# netnode_v3.net
KiCad netlist of a schematic drawn in EAGLE
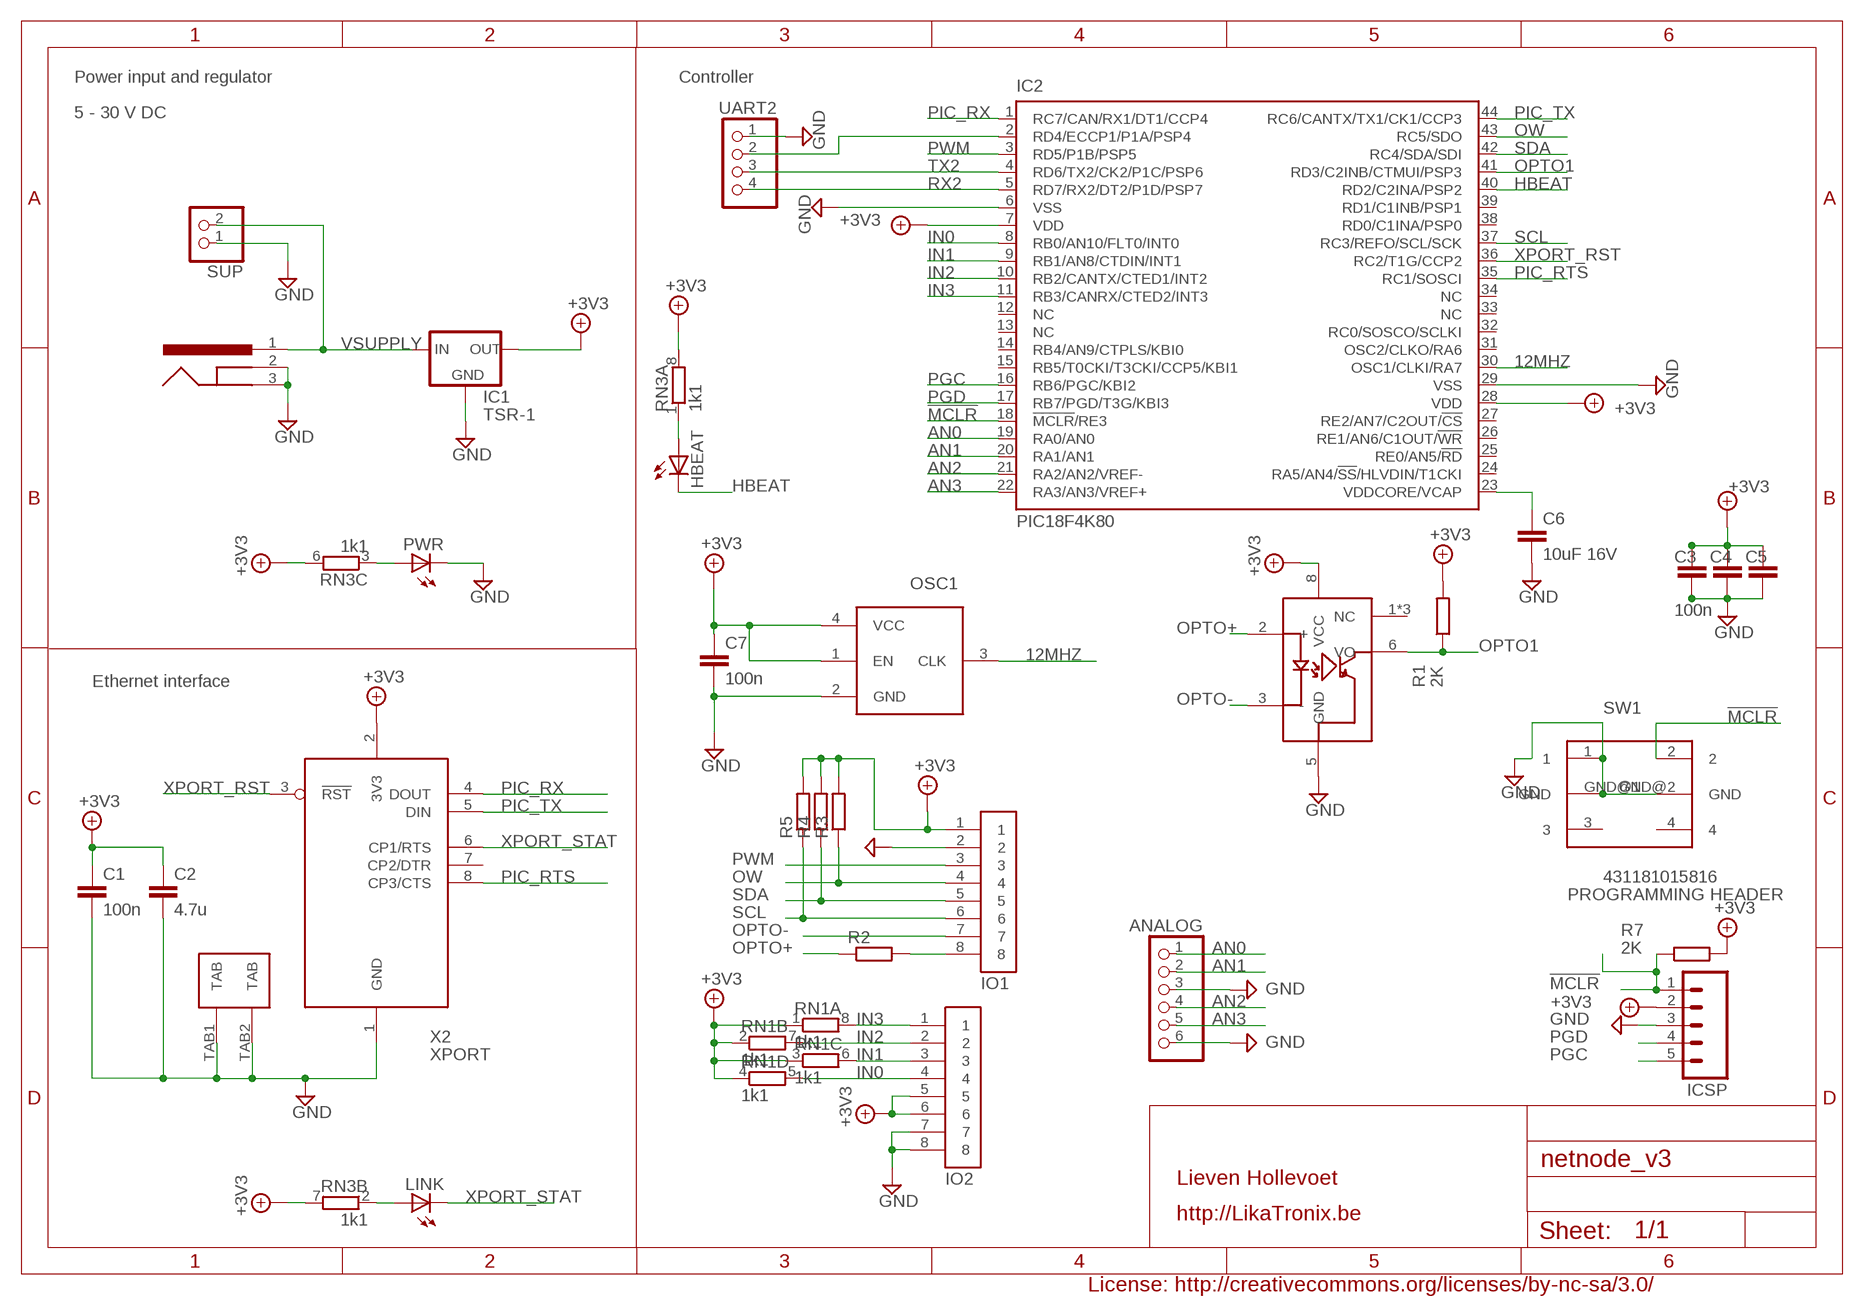
[diagram p0: schematic, sheet 1]

(export (version "E")
  (design (tool "Eeschema 10.0.6"))
  (components
    (comp (ref "ANALOG")
      (value "PINHD-1X6")
      (footprint "eagle-import:1X06")
      (libsource (lib "eagle-import") (part "PINHD-1X6"))
    )
    (comp (ref "C1")
      (value "100n")
      (footprint "eagle-import:C0805")
      (fields (field (name "MF") "AVX") (field (name "MPN") "08055C104JAT2A"))
      (libsource (lib "eagle-import") (part "rcl_C-EUC0805"))
    )
    (comp (ref "C2")
      (value "4.7u")
      (footprint "eagle-import:C0805")
      (fields (field (name "MF") "AVX") (field (name "MPN") "0805YD475KAT2A"))
      (libsource (lib "eagle-import") (part "C-EUC0805"))
    )
    (comp (ref "C3")
      (value "100n")
      (footprint "eagle-import:C0805")
      (fields (field (name "MF") "AVX") (field (name "MPN") "08055C104JAT2A"))
      (libsource (lib "eagle-import") (part "rcl_C-EUC0805"))
    )
    (comp (ref "C4")
      (value "100n")
      (footprint "eagle-import:C0805")
      (fields (field (name "MF") "AVX") (field (name "MPN") "08055C104JAT2A"))
      (libsource (lib "eagle-import") (part "rcl_C-EUC0805"))
    )
    (comp (ref "C5")
      (value "100n")
      (footprint "eagle-import:C0805")
      (fields (field (name "MF") "AVX") (field (name "MPN") "08055C104JAT2A"))
      (libsource (lib "eagle-import") (part "rcl_C-EUC0805"))
    )
    (comp (ref "C6")
      (value "10uF 16V")
      (footprint "eagle-import:C1206")
      (fields (field (name "MF") "KEMET") (field (name "MPN") "C1206C106K4PAC-TU"))
      (libsource (lib "eagle-import") (part "C-EUC1206"))
    )
    (comp (ref "C7")
      (value "100n")
      (footprint "eagle-import:C0805")
      (fields (field (name "MF") "AVX") (field (name "MPN") "08055C104JAT2A"))
      (libsource (lib "eagle-import") (part "rcl_C-EUC0805"))
    )
    (comp (ref "HBEAT")
      (value "LEDCHIPLED_1206")
      (footprint "eagle-import:CHIPLED_1206")
      (fields (field (name "MF") "KINGBRIGHT") (field (name "MPN") "KP-3216EC"))
      (libsource (lib "eagle-import") (part "LEDCHIPLED_1206"))
    )
    (comp (ref "IC1")
      (value "TSR-1")
      (footprint "eagle-import:TSR1-SIPS")
      (fields (field (name "MF") "TRACOPOWER") (field (name "MPN") "TSR 1-2433"))
      (libsource (lib "eagle-import") (part "TSR-1"))
    )
    (comp (ref "IC2")
      (value "PIC18F4K80")
      (footprint "eagle-import:TQFP44")
      (fields (field (name "MF") "MICROCHIP") (field (name "MPN") "PIC18F45K80-I/PT"))
      (libsource (lib "eagle-import") (part "PIC18F4K80"))
    )
    (comp (ref "IC3")
      (value "FOD060L")
      (footprint "eagle-import:SO-08")
      (libsource (lib "eagle-import") (part "FOD060L"))
    )
    (comp (ref "ICSP")
      (value "ICSP")
      (footprint "eagle-import:1X05")
      (libsource (lib "eagle-import") (part "M05"))
    )
    (comp (ref "IO1")
      (value "SCREW_TERMINAL")
      (footprint "eagle-import:SCREW_TERMINAL_8PINS")
      (fields (field (name "MF") "PHOENIX CONTACT") (field (name "MPN") "1725711"))
      (libsource (lib "eagle-import") (part "SCREW_TERMINAL"))
    )
    (comp (ref "IO2")
      (value "SCREW_TERMINAL")
      (footprint "eagle-import:SCREW_TERMINAL_8PINS")
      (fields (field (name "MF") "PHOENIX CONTACT") (field (name "MPN") "1725711"))
      (libsource (lib "eagle-import") (part "SCREW_TERMINAL"))
    )
    (comp (ref "LINK")
      (value "LEDCHIPLED_1206")
      (footprint "eagle-import:CHIPLED_1206")
      (fields (field (name "MF") "KINGBRIGHT") (field (name "MPN") "KP-3216EC"))
      (libsource (lib "eagle-import") (part "LEDCHIPLED_1206"))
    )
    (comp (ref "OSC1")
      (value "TXC - 7X-12.000MBB-T")
      (footprint "eagle-import:7W_7X5")
      (fields
        (field (name "MF") "TXC")
        (field (name "MPN") "7X-12.000MBB-T")
        (field (name "OC_FARNELL") "1842099")
      )
      (libsource (lib "eagle-import") (part "OSC7W_7X5"))
    )
    (comp (ref "PWR")
      (value "LEDCHIPLED_1206")
      (footprint "eagle-import:CHIPLED_1206")
      (fields (field (name "MF") "KINGBRIGHT") (field (name "MPN") "KP-3216EC"))
      (libsource (lib "eagle-import") (part "LEDCHIPLED_1206"))
    )
    (comp (ref "R1")
      (value "2K")
      (footprint "eagle-import:R0805")
      (fields (field (name "MF") "BOURNS") (field (name "MPN") "CR0603-FX-2001ELF"))
      (libsource (lib "eagle-import") (part "R-EU_R0805"))
    )
    (comp (ref "R2")
      (value "R-EU_M0805")
      (footprint "eagle-import:M0805")
      (libsource (lib "eagle-import") (part "R-EU_M0805"))
    )
    (comp (ref "R3")
      (value "R-EU_R0603")
      (footprint "eagle-import:R0603")
      (libsource (lib "eagle-import") (part "R-EU_R0603"))
    )
    (comp (ref "R4")
      (value "R-EU_R0603")
      (footprint "eagle-import:R0603")
      (libsource (lib "eagle-import") (part "R-EU_R0603"))
    )
    (comp (ref "R5")
      (value "R-EU_R0603")
      (footprint "eagle-import:R0603")
      (libsource (lib "eagle-import") (part "R-EU_R0603"))
    )
    (comp (ref "R7")
      (value "2K")
      (footprint "eagle-import:R0805")
      (fields (field (name "MF") "BOURNS") (field (name "MPN") "CR0603-FX-2001ELF"))
      (libsource (lib "eagle-import") (part "R-EU_R0805"))
    )
    (comp (ref "RN1")
      (value "1k1")
      (footprint "eagle-import:RN8P-4R-CRA06S")
      (fields
        (field (name "MF") "PANASONIC")
        (field (name "MPN") "EXB38V102JV")
        (field (name "OC_FARNELL") "2060100")
      )
      (libsource (lib "eagle-import") (part "RNETWORK"))
    )
    (comp (ref "RN3")
      (value "1k1")
      (footprint "eagle-import:RN8P-4R-CRA06S")
      (fields
        (field (name "MF") "PANASONIC")
        (field (name "MPN") "EXB38V102JV")
        (field (name "OC_FARNELL") "2060100")
      )
      (libsource (lib "eagle-import") (part "RNETWORK"))
    )
    (comp (ref "SUP")
      (value "PINHD-1X2")
      (footprint "eagle-import:1X02")
      (libsource (lib "eagle-import") (part "PINHD-1X2"))
    )
    (comp (ref "SW1")
      (value "431181015816")
      (footprint "eagle-import:431181015816")
      (libsource (lib "eagle-import") (part "431181015816"))
    )
    (comp (ref "UART2")
      (value "PINHD-1X4")
      (footprint "eagle-import:1X04")
      (libsource (lib "eagle-import") (part "PINHD-1X4"))
    )
    (comp (ref "X1")
      (value "DC10R")
      (footprint "eagle-import:DC10R")
      (fields (field (name "MF") "CLIFF ELECTRONIC COMPONENTS") (field (name "MPN") "DC10A"))
      (libsource (lib "eagle-import") (part "DC10R"))
    )
    (comp (ref "X2")
      (value "XPORT")
      (footprint "eagle-import:XPORT")
      (fields (field (name "OC_FARNELL") "unknown"))
      (libsource (lib "eagle-import") (part "XPORT"))
    )
  )
  (nets
    (net (code "1") (name "+3V3") (class "Default")
      (node (ref "C1") (pin "1") (pinfunction "1_1") (pintype "passive"))
      (node (ref "C2") (pin "1") (pinfunction "1_1") (pintype "passive"))
      (node (ref "C3") (pin "1") (pinfunction "1_1") (pintype "passive"))
      (node (ref "C4") (pin "1") (pinfunction "1_1") (pintype "passive"))
      (node (ref "C5") (pin "1") (pinfunction "1_1") (pintype "passive"))
      (node (ref "C7") (pin "1") (pinfunction "1_1") (pintype "passive"))
      (node (ref "IC1") (pin "3") (pinfunction "OUT_3") (pintype "passive"))
      (node (ref "IC2") (pin "28") (pinfunction "VDD_28") (pintype "power_in"))
      (node (ref "IC2") (pin "7") (pinfunction "VDD_7") (pintype "power_in"))
      (node (ref "IC3") (pin "8") (pinfunction "VCC_8") (pintype "power_in"))
      (node (ref "ICSP") (pin "2") (pinfunction "2_2") (pintype "passive"))
      (node (ref "IO1") (pin "1") (pinfunction "1_1") (pintype "bidirectional"))
      (node (ref "IO2") (pin "5") (pinfunction "5_5") (pintype "bidirectional"))
      (node (ref "IO2") (pin "6") (pinfunction "6_6") (pintype "bidirectional"))
      (node (ref "OSC1") (pin "1") (pinfunction "EN_1") (pintype "input"))
      (node (ref "OSC1") (pin "4") (pinfunction "VCC_4") (pintype "power_in"))
      (node (ref "R1") (pin "2") (pinfunction "2_2") (pintype "passive"))
      (node (ref "R3") (pin "2") (pinfunction "2_2") (pintype "passive"))
      (node (ref "R4") (pin "2") (pinfunction "2_2") (pintype "passive"))
      (node (ref "R5") (pin "2") (pinfunction "2_2") (pintype "passive"))
      (node (ref "R7") (pin "2") (pinfunction "2_2") (pintype "passive"))
      (node (ref "RN1") (pin "1") (pinfunction "1_1") (pintype "passive"))
      (node (ref "RN1") (pin "2") (pinfunction "1_2") (pintype "passive"))
      (node (ref "RN1") (pin "3") (pinfunction "1_3") (pintype "passive"))
      (node (ref "RN1") (pin "4") (pinfunction "1_4") (pintype "passive"))
      (node (ref "RN3") (pin "6") (pinfunction "2_6") (pintype "passive"))
      (node (ref "RN3") (pin "7") (pinfunction "2_7") (pintype "passive"))
      (node (ref "RN3") (pin "8") (pinfunction "2_8") (pintype "passive"))
      (node (ref "X2") (pin "2") (pinfunction "3V3_2") (pintype "power_in"))
    )
    (net (code "2") (name "/12MHZ") (class "Default")
      (node (ref "IC2") (pin "30") (pinfunction "OSC1/CLKI/RA7_30") (pintype "input"))
      (node (ref "OSC1") (pin "3") (pinfunction "CLK_3") (pintype "output"))
    )
    (net (code "3") (name "/AN0") (class "Default")
      (node (ref "ANALOG") (pin "1") (pinfunction "1_1") (pintype "passive"))
      (node (ref "IC2") (pin "19") (pinfunction "RA0/AN0_19") (pintype "bidirectional"))
    )
    (net (code "4") (name "/AN1") (class "Default")
      (node (ref "ANALOG") (pin "2") (pinfunction "2_2") (pintype "passive"))
      (node (ref "IC2") (pin "20") (pinfunction "RA1/AN1_20") (pintype "bidirectional"))
    )
    (net (code "5") (name "/AN2") (class "Default")
      (node (ref "ANALOG") (pin "4") (pinfunction "4_4") (pintype "passive"))
      (node (ref "IC2") (pin "21") (pinfunction "RA2/AN2/VREF-_21") (pintype "bidirectional"))
    )
    (net (code "6") (name "/AN3") (class "Default")
      (node (ref "ANALOG") (pin "5") (pinfunction "5_5") (pintype "passive"))
      (node (ref "IC2") (pin "22") (pinfunction "RA3/AN3/VREF+_22") (pintype "bidirectional"))
    )
    (net (code "7") (name "/HBEAT") (class "Default")
      (node (ref "HBEAT") (pin "C") (pinfunction "C_C") (pintype "passive"))
      (node (ref "IC2") (pin "40") (pinfunction "RD2/C2INA/PSP2_40") (pintype "bidirectional"))
    )
    (net (code "8") (name "/IN0") (class "Default")
      (node (ref "IC2") (pin "8") (pinfunction "RB0/AN10/FLT0/INT0_8") (pintype "bidirectional"))
      (node (ref "IO2") (pin "4") (pinfunction "4_4") (pintype "bidirectional"))
      (node (ref "RN1") (pin "5") (pinfunction "2_5") (pintype "passive"))
    )
    (net (code "9") (name "/IN1") (class "Default")
      (node (ref "IC2") (pin "9") (pinfunction "RB1/AN8/CTDIN/INT1_9") (pintype "bidirectional"))
      (node (ref "IO2") (pin "3") (pinfunction "3_3") (pintype "bidirectional"))
      (node (ref "RN1") (pin "6") (pinfunction "2_6") (pintype "passive"))
    )
    (net (code "10") (name "/IN2") (class "Default")
      (node (ref "IC2") (pin "10") (pinfunction "RB2/CANTX/CTED1/INT2_10") (pintype "bidirectional"))
      (node (ref "IO2") (pin "2") (pinfunction "2_2") (pintype "bidirectional"))
      (node (ref "RN1") (pin "7") (pinfunction "2_7") (pintype "passive"))
    )
    (net (code "11") (name "/IN3") (class "Default")
      (node (ref "IC2") (pin "11") (pinfunction "RB3/CANRX/CTED2/INT3_11") (pintype "bidirectional"))
      (node (ref "IO2") (pin "1") (pinfunction "1_1") (pintype "bidirectional"))
      (node (ref "RN1") (pin "8") (pinfunction "2_8") (pintype "passive"))
    )
    (net (code "12") (name "/OPTO+") (class "Default")
      (node (ref "IC3") (pin "2") (pinfunction "+_2") (pintype "bidirectional"))
      (node (ref "R2") (pin "1") (pinfunction "1_1") (pintype "passive"))
    )
    (net (code "13") (name "/OPTO-") (class "Default")
      (node (ref "IC3") (pin "3") (pinfunction "-_3") (pintype "bidirectional"))
      (node (ref "IO1") (pin "7") (pinfunction "7_7") (pintype "bidirectional"))
    )
    (net (code "14") (name "/OPTO1") (class "Default")
      (node (ref "IC2") (pin "41") (pinfunction "RD3/C2INB/CTMUI/PSP3_41") (pintype "bidirectional"))
      (node (ref "IC3") (pin "6") (pinfunction "VO_6") (pintype "output"))
      (node (ref "R1") (pin "1") (pinfunction "1_1") (pintype "passive"))
    )
    (net (code "15") (name "/OW") (class "Default")
      (node (ref "IC2") (pin "43") (pinfunction "RC5/SDO_43") (pintype "bidirectional"))
      (node (ref "IO1") (pin "4") (pinfunction "4_4") (pintype "bidirectional"))
      (node (ref "R3") (pin "1") (pinfunction "1_1") (pintype "passive"))
    )
    (net (code "16") (name "/PGC") (class "Default")
      (node (ref "IC2") (pin "16") (pinfunction "RB6/PGC/KBI2_16") (pintype "bidirectional"))
      (node (ref "ICSP") (pin "5") (pinfunction "5_5") (pintype "passive"))
    )
    (net (code "17") (name "/PGD") (class "Default")
      (node (ref "IC2") (pin "17") (pinfunction "RB7/PGD/T3G/KBI3_17") (pintype "bidirectional"))
      (node (ref "ICSP") (pin "4") (pinfunction "4_4") (pintype "passive"))
    )
    (net (code "18") (name "/PIC_RTS") (class "Default")
      (node (ref "IC2") (pin "35") (pinfunction "RC1/SOSCI_35") (pintype "bidirectional"))
      (node (ref "X2") (pin "8") (pinfunction "CP3/CTS_8") (pintype "input"))
    )
    (net (code "19") (name "/PIC_RX") (class "Default")
      (node (ref "IC2") (pin "1") (pinfunction "RC7/CAN/RX1/DT1/CCP4_1") (pintype "bidirectional"))
      (node (ref "X2") (pin "4") (pinfunction "DOUT_4") (pintype "output"))
    )
    (net (code "20") (name "/PIC_TX") (class "Default")
      (node (ref "IC2") (pin "44") (pinfunction "RC6/CANTX/TX1/CK1/CCP3_44") (pintype "bidirectional"))
      (node (ref "X2") (pin "5") (pinfunction "DIN_5") (pintype "input"))
    )
    (net (code "21") (name "/PWM") (class "Default")
      (node (ref "IC2") (pin "3") (pinfunction "RD5/P1B/PSP5_3") (pintype "bidirectional"))
      (node (ref "IO1") (pin "3") (pinfunction "3_3") (pintype "bidirectional"))
    )
    (net (code "22") (name "/RX2") (class "Default")
      (node (ref "IC2") (pin "5") (pinfunction "RD7/RX2/DT2/P1D/PSP7_5") (pintype "bidirectional"))
      (node (ref "UART2") (pin "4") (pinfunction "4_4") (pintype "passive"))
    )
    (net (code "23") (name "/SCL") (class "Default")
      (node (ref "IC2") (pin "37") (pinfunction "RC3/REFO/SCL/SCK_37") (pintype "bidirectional"))
      (node (ref "IO1") (pin "6") (pinfunction "6_6") (pintype "bidirectional"))
      (node (ref "R5") (pin "1") (pinfunction "1_1") (pintype "passive"))
    )
    (net (code "24") (name "/SDA") (class "Default")
      (node (ref "IC2") (pin "42") (pinfunction "RC4/SDA/SDI_42") (pintype "bidirectional"))
      (node (ref "IO1") (pin "5") (pinfunction "5_5") (pintype "bidirectional"))
      (node (ref "R4") (pin "1") (pinfunction "1_1") (pintype "passive"))
    )
    (net (code "25") (name "/TX2") (class "Default")
      (node (ref "IC2") (pin "4") (pinfunction "RD6/TX2/CK2/P1C/PSP6_4") (pintype "bidirectional"))
      (node (ref "UART2") (pin "3") (pinfunction "3_3") (pintype "passive"))
    )
    (net (code "26") (name "/VSUPPLY") (class "Default")
      (node (ref "IC1") (pin "1") (pinfunction "IN_1") (pintype "input"))
      (node (ref "SUP") (pin "2") (pinfunction "2_2") (pintype "passive"))
      (node (ref "X1") (pin "1") (pinfunction "CENTER_1") (pintype "power_in"))
    )
    (net (code "27") (name "/XPORT_RST") (class "Default")
      (node (ref "IC2") (pin "36") (pinfunction "RC2/T1G/CCP2_36") (pintype "bidirectional"))
      (node (ref "X2") (pin "3") (pinfunction "~{RST}_3") (pintype "input"))
    )
    (net (code "28") (name "/XPORT_STAT") (class "Default")
      (node (ref "LINK") (pin "C") (pinfunction "C_C") (pintype "passive"))
      (node (ref "X2") (pin "6") (pinfunction "CP1/RTS_6") (pintype "bidirectional"))
    )
    (net (code "29") (name "/~{MCLR}") (class "Default")
      (node (ref "IC2") (pin "18") (pinfunction "~{MCLR}/RE3_18") (pintype "input"))
      (node (ref "ICSP") (pin "1") (pinfunction "1_1") (pintype "passive"))
      (node (ref "R7") (pin "1") (pinfunction "1_1") (pintype "passive"))
      (node (ref "SW1") (pin "2") (pinfunction "2_2") (pintype "bidirectional"))
    )
    (net (code "30") (name "GND") (class "Default")
      (node (ref "ANALOG") (pin "3") (pinfunction "3_3") (pintype "passive"))
      (node (ref "ANALOG") (pin "6") (pinfunction "6_6") (pintype "passive"))
      (node (ref "C1") (pin "2") (pinfunction "2_2") (pintype "passive"))
      (node (ref "C2") (pin "2") (pinfunction "2_2") (pintype "passive"))
      (node (ref "C3") (pin "2") (pinfunction "2_2") (pintype "passive"))
      (node (ref "C4") (pin "2") (pinfunction "2_2") (pintype "passive"))
      (node (ref "C5") (pin "2") (pinfunction "2_2") (pintype "passive"))
      (node (ref "C6") (pin "2") (pinfunction "2_2") (pintype "passive"))
      (node (ref "C7") (pin "2") (pinfunction "2_2") (pintype "passive"))
      (node (ref "IC1") (pin "2") (pinfunction "GND_2") (pintype "input"))
      (node (ref "IC2") (pin "29") (pinfunction "VSS_29") (pintype "power_in"))
      (node (ref "IC2") (pin "6") (pinfunction "VSS_6") (pintype "power_in"))
      (node (ref "IC3") (pin "5") (pinfunction "GND_5") (pintype "power_in"))
      (node (ref "ICSP") (pin "3") (pinfunction "3_3") (pintype "passive"))
      (node (ref "IO1") (pin "2") (pinfunction "2_2") (pintype "bidirectional"))
      (node (ref "IO2") (pin "7") (pinfunction "7_7") (pintype "bidirectional"))
      (node (ref "IO2") (pin "8") (pinfunction "8_8") (pintype "bidirectional"))
      (node (ref "OSC1") (pin "2") (pinfunction "GND_2") (pintype "power_in"))
      (node (ref "PWR") (pin "C") (pinfunction "C_C") (pintype "passive"))
      (node (ref "SUP") (pin "1") (pinfunction "1_1") (pintype "passive"))
      (node (ref "SW1") (pin "1") (pinfunction "1_1") (pintype "bidirectional"))
      (node (ref "SW1") (pin "GND@1") (pinfunction "GND_GND@1") (pintype "bidirectional"))
      (node (ref "SW1") (pin "GND@2") (pinfunction "GND_GND@2") (pintype "bidirectional"))
      (node (ref "UART2") (pin "1") (pinfunction "1_1") (pintype "passive"))
      (node (ref "X1") (pin "2") (pinfunction "CONTACT_2") (pintype "bidirectional"))
      (node (ref "X1") (pin "3") (pinfunction "SHIELD_3") (pintype "power_in"))
      (node (ref "X2") (pin "1") (pinfunction "GND_1") (pintype "power_in"))
      (node (ref "X2") (pin "TAB1") (pinfunction "TAB_TAB1") (pintype "power_in"))
      (node (ref "X2") (pin "TAB2") (pinfunction "TAB_TAB2") (pintype "power_in"))
    )
    (net (code "31") (name "Net-(HBEAT-PadA)") (class "Default")
      (node (ref "HBEAT") (pin "A") (pinfunction "A_A") (pintype "passive"))
      (node (ref "RN3") (pin "1") (pinfunction "1_1") (pintype "passive"))
    )
    (net (code "32") (name "Net-(IC2-RD4{slash}ECCP1{slash}P1A{slash}PSP4)") (class "Default")
      (node (ref "IC2") (pin "2") (pinfunction "RD4/ECCP1/P1A/PSP4_2") (pintype "bidirectional"))
      (node (ref "UART2") (pin "2") (pinfunction "2_2") (pintype "passive"))
    )
    (net (code "33") (name "Net-(IC2-VDDCORE{slash}VCAP)") (class "Default")
      (node (ref "C6") (pin "1") (pinfunction "1_1") (pintype "passive"))
      (node (ref "IC2") (pin "23") (pinfunction "VDDCORE/VCAP_23") (pintype "bidirectional"))
    )
    (net (code "34") (name "Net-(IO1-Pad8)") (class "Default")
      (node (ref "IO1") (pin "8") (pinfunction "8_8") (pintype "bidirectional"))
      (node (ref "R2") (pin "2") (pinfunction "2_2") (pintype "passive"))
    )
    (net (code "35") (name "Net-(RN3B-1)") (class "Default")
      (node (ref "LINK") (pin "A") (pinfunction "A_A") (pintype "passive"))
      (node (ref "RN3") (pin "2") (pinfunction "1_2") (pintype "passive"))
    )
    (net (code "36") (name "Net-(RN3C-1)") (class "Default")
      (node (ref "PWR") (pin "A") (pinfunction "A_A") (pintype "passive"))
      (node (ref "RN3") (pin "3") (pinfunction "1_3") (pintype "passive"))
    )
    (net (code "37") (name "unconnected-(IC2-NC-Pad12)") (class "Default")
      (node (ref "IC2") (pin "12") (pinfunction "NC_12") (pintype "no_connect"))
    )
    (net (code "38") (name "unconnected-(IC2-NC-Pad13)") (class "Default")
      (node (ref "IC2") (pin "13") (pinfunction "NC_13") (pintype "no_connect"))
    )
    (net (code "39") (name "unconnected-(IC2-NC-Pad33)") (class "Default")
      (node (ref "IC2") (pin "33") (pinfunction "NC_33") (pintype "no_connect"))
    )
    (net (code "40") (name "unconnected-(IC2-NC-Pad34)") (class "Default")
      (node (ref "IC2") (pin "34") (pinfunction "NC_34") (pintype "no_connect"))
    )
    (net (code "41") (name "unconnected-(IC2-OSC2{slash}CLKO{slash}RA6-Pad31)") (class "Default")
      (node (ref "IC2") (pin "31") (pinfunction "OSC2/CLKO/RA6_31") (pintype "output"))
    )
    (net (code "42") (name "unconnected-(IC2-RA5{slash}AN4{slash}~{SS}{slash}HLVDIN{slash}T1CKI-Pad24)") (class "Default")
      (node (ref "IC2") (pin "24") (pinfunction "RA5/AN4/~{SS}/HLVDIN/T1CKI_24") (pintype "bidirectional"))
    )
    (net (code "43") (name "unconnected-(IC2-RB4{slash}AN9{slash}CTPLS{slash}KBI0-Pad14)") (class "Default")
      (node (ref "IC2") (pin "14") (pinfunction "RB4/AN9/CTPLS/KBI0_14") (pintype "bidirectional"))
    )
    (net (code "44") (name "unconnected-(IC2-RB5{slash}T0CKI{slash}T3CKI{slash}CCP5{slash}KBI1-Pad15)") (class "Default")
      (node (ref "IC2") (pin "15") (pinfunction "RB5/T0CKI/T3CKI/CCP5/KBI1_15") (pintype "bidirectional"))
    )
    (net (code "45") (name "unconnected-(IC2-RC0{slash}SOSCO{slash}SCLKI-Pad32)") (class "Default")
      (node (ref "IC2") (pin "32") (pinfunction "RC0/SOSCO/SCLKI_32") (pintype "bidirectional"))
    )
    (net (code "46") (name "unconnected-(IC2-RD0{slash}C1INA{slash}PSP0-Pad38)") (class "Default")
      (node (ref "IC2") (pin "38") (pinfunction "RD0/C1INA/PSP0_38") (pintype "bidirectional"))
    )
    (net (code "47") (name "unconnected-(IC2-RD1{slash}C1INB{slash}PSP1-Pad39)") (class "Default")
      (node (ref "IC2") (pin "39") (pinfunction "RD1/C1INB/PSP1_39") (pintype "bidirectional"))
    )
    (net (code "48") (name "unconnected-(IC2-RE0{slash}AN5{slash}~{RD}-Pad25)") (class "Default")
      (node (ref "IC2") (pin "25") (pinfunction "RE0/AN5/~{RD}_25") (pintype "bidirectional"))
    )
    (net (code "49") (name "unconnected-(IC2-RE1{slash}AN6{slash}C1OUT{slash}~{WR}-Pad26)") (class "Default")
      (node (ref "IC2") (pin "26") (pinfunction "RE1/AN6/C1OUT/~{WR}_26") (pintype "bidirectional"))
    )
    (net (code "50") (name "unconnected-(IC2-RE2{slash}AN7{slash}C2OUT{slash}~{CS}-Pad27)") (class "Default")
      (node (ref "IC2") (pin "27") (pinfunction "RE2/AN7/C2OUT/~{CS}_27") (pintype "bidirectional"))
    )
    (net (code "51") (name "unconnected-(IC3-NC-Pad1)") (class "Default")
      (node (ref "IC3") (pin "1") (pinfunction "NC_1") (pintype "no_connect"))
    )
    (net (code "52") (name "unconnected-(IC3-NC-Pad4)") (class "Default")
      (node (ref "IC3") (pin "4") (pinfunction "NC_4") (pintype "no_connect"))
    )
    (net (code "53") (name "unconnected-(IC3-NC-Pad7)") (class "Default")
      (node (ref "IC3") (pin "7") (pinfunction "NC_7") (pintype "no_connect"))
    )
    (net (code "54") (name "unconnected-(SW1-Pad3)") (class "Default")
      (node (ref "SW1") (pin "3") (pinfunction "3_3") (pintype "bidirectional"))
    )
    (net (code "55") (name "unconnected-(SW1-Pad4)") (class "Default")
      (node (ref "SW1") (pin "4") (pinfunction "4_4") (pintype "bidirectional"))
    )
    (net (code "56") (name "unconnected-(X2A-CP2{slash}DTR-Pad7)") (class "Default")
      (node (ref "X2") (pin "7") (pinfunction "CP2/DTR_7") (pintype "bidirectional"))
    )
  )
)
